# 12_-POWER_CONNECTORS.net
KiCad netlist of a schematic drawn in Altium Designer
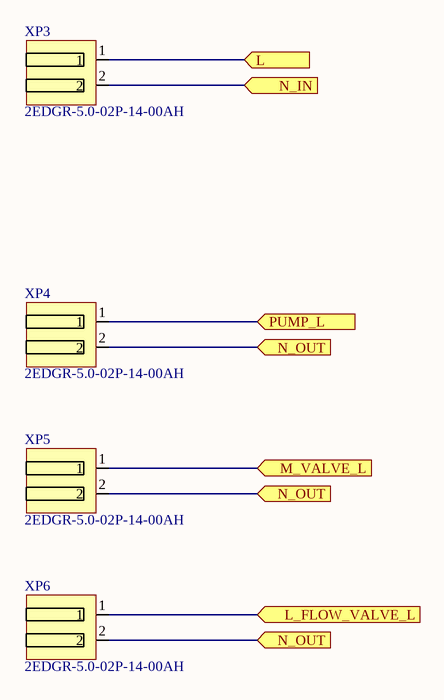
[diagram p0: [12]-POWER_CONNECTORS.SchDoc]

(export (version "E")
  (design (tool "Eeschema 10.0.6"))
  (components
    (comp (ref "XP3")
      (value "2EDGR-5.0-02P-14-00AH")
      (footprint "2EDGR-5.0")
      (libsource (lib "fizik_lib") (part "2EDGR-5.0-02P-14-00AH"))
    )
    (comp (ref "XP4")
      (value "2EDGR-5.0-02P-14-00AH")
      (footprint "2EDGR-5.0")
      (libsource (lib "fizik_lib") (part "2EDGR-5.0-02P-14-00AH"))
    )
    (comp (ref "XP5")
      (value "2EDGR-5.0-02P-14-00AH")
      (footprint "2EDGR-5.0")
      (libsource (lib "fizik_lib") (part "2EDGR-5.0-02P-14-00AH"))
    )
    (comp (ref "XP6")
      (value "2EDGR-5.0-02P-14-00AH")
      (footprint "2EDGR-5.0")
      (libsource (lib "fizik_lib") (part "2EDGR-5.0-02P-14-00AH"))
    )
  )
  (nets
    (net (code "1") (name "/L") (class "Default")
      (node (ref "XP3") (pin "1") (pinfunction "1_1") (pintype "passive"))
    )
    (net (code "2") (name "/L_FLOW_VALVE_L") (class "Default")
      (node (ref "XP6") (pin "1") (pinfunction "1_1") (pintype "passive"))
    )
    (net (code "3") (name "/M_VALVE_L") (class "Default")
      (node (ref "XP5") (pin "1") (pinfunction "1_1") (pintype "passive"))
    )
    (net (code "4") (name "/N_IN") (class "Default")
      (node (ref "XP3") (pin "2") (pinfunction "2_2") (pintype "passive"))
    )
    (net (code "5") (name "/N_OUT") (class "Default")
      (node (ref "XP4") (pin "2") (pinfunction "2_2") (pintype "passive"))
      (node (ref "XP5") (pin "2") (pinfunction "2_2") (pintype "passive"))
      (node (ref "XP6") (pin "2") (pinfunction "2_2") (pintype "passive"))
    )
    (net (code "6") (name "/PUMP_L") (class "Default")
      (node (ref "XP4") (pin "1") (pinfunction "1_1") (pintype "passive"))
    )
  )
)
